# Strvo_Tester_STM_v4.net
KiCad netlist of a schematic drawn in EAGLE
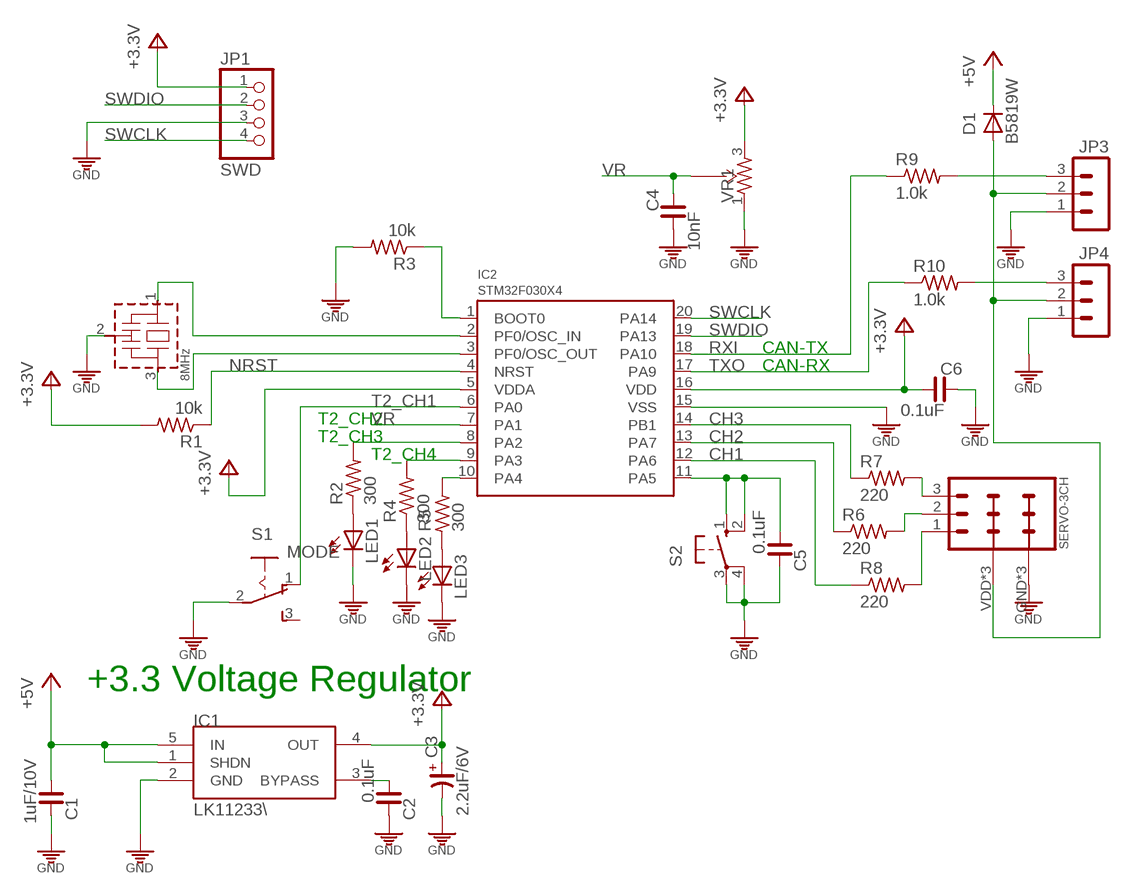
[diagram p0: schematic, sheet 1]

(export (version "E")
  (design (tool "Eeschema 10.0.6"))
  (components
    (comp (ref "C1")
      (value "1uF/10V")
      (footprint "eagle-import:C0603")
      (libsource (lib "eagle-import") (part "C_0603"))
    )
    (comp (ref "C2")
      (value "0.1uF")
      (footprint "eagle-import:C0603")
      (libsource (lib "eagle-import") (part "C_0603"))
    )
    (comp (ref "C3")
      (value "2.2uF/6V")
      (footprint "eagle-import:C2012_T")
      (libsource (lib "eagle-import") (part "CP_2012"))
    )
    (comp (ref "C4")
      (value "10nF")
      (footprint "eagle-import:C0603")
      (libsource (lib "eagle-import") (part "C_0603"))
    )
    (comp (ref "C5")
      (value "0.1uF")
      (footprint "eagle-import:C0603")
      (libsource (lib "eagle-import") (part "C_0603"))
    )
    (comp (ref "C6")
      (value "0.1uF")
      (footprint "eagle-import:C0603")
      (libsource (lib "eagle-import") (part "C_0603"))
    )
    (comp (ref "D1")
      (value "B5819W")
      (footprint "eagle-import:SOD323")
      (libsource (lib "eagle-import") (part "B5189WN"))
    )
    (comp (ref "IC1")
      (value "LK11233\\")
      (footprint "eagle-import:SOT23-5L")
      (libsource (lib "eagle-import") (part "LK112XX"))
    )
    (comp (ref "IC2")
      (value "STM32F030X4")
      (footprint "eagle-import:TSSOP20")
      (libsource (lib "eagle-import") (part "STM32F030X4"))
    )
    (comp (ref "JP1")
      (value "SWD")
      (footprint "eagle-import:1X04M")
      (libsource (lib "eagle-import") (part "PINHD-1X4M"))
    )
    (comp (ref "JP2")
      (value "SERVO-3CH")
      (footprint "eagle-import:SERVO-3CH1")
      (libsource (lib "eagle-import") (part "SERVO-3CH"))
    )
    (comp (ref "JP3")
      (value "MA03-1SMALL")
      (footprint "eagle-import:MA03-1-S")
      (libsource (lib "eagle-import") (part "MA03-1SMALL"))
    )
    (comp (ref "JP4")
      (value "MA03-1SMALL")
      (footprint "eagle-import:MA03-1-S")
      (libsource (lib "eagle-import") (part "MA03-1SMALL"))
    )
    (comp (ref "LED1")
      (value "LED3MM")
      (footprint "eagle-import:LED3MM")
      (libsource (lib "eagle-import") (part "LED3MM"))
    )
    (comp (ref "LED2")
      (value "LED3MM")
      (footprint "eagle-import:LED3MM")
      (libsource (lib "eagle-import") (part "LED3MM"))
    )
    (comp (ref "LED3")
      (value "LED3MM")
      (footprint "eagle-import:LED3MM")
      (libsource (lib "eagle-import") (part "LED3MM"))
    )
    (comp (ref "Q1")
      (value "8MHz")
      (footprint "eagle-import:CSTLA_X")
      (libsource (lib "eagle-import") (part "X-TAL-SMALLCSTCE16M00V53"))
    )
    (comp (ref "R1")
      (value "10k")
      (footprint "eagle-import:R0603")
      (libsource (lib "eagle-import") (part "R-US_R1608"))
    )
    (comp (ref "R2")
      (value "300")
      (footprint "eagle-import:R0603")
      (libsource (lib "eagle-import") (part "R-US_R1608"))
    )
    (comp (ref "R3")
      (value "10k")
      (footprint "eagle-import:R0603")
      (libsource (lib "eagle-import") (part "R-US_R1608"))
    )
    (comp (ref "R4")
      (value "300")
      (footprint "eagle-import:R0603")
      (libsource (lib "eagle-import") (part "R-US_R1608"))
    )
    (comp (ref "R5")
      (value "300")
      (footprint "eagle-import:R0603")
      (libsource (lib "eagle-import") (part "R_0603"))
    )
    (comp (ref "R6")
      (value "220")
      (footprint "eagle-import:R0603")
      (libsource (lib "eagle-import") (part "R-US_R1608"))
    )
    (comp (ref "R7")
      (value "220")
      (footprint "eagle-import:R0603")
      (libsource (lib "eagle-import") (part "R-US_R1608"))
    )
    (comp (ref "R8")
      (value "220")
      (footprint "eagle-import:R0603")
      (libsource (lib "eagle-import") (part "R-US_R1608"))
    )
    (comp (ref "R9")
      (value "1.0k")
      (footprint "eagle-import:R0603")
      (libsource (lib "eagle-import") (part "R-US_R1608"))
    )
    (comp (ref "R10")
      (value "1.0k")
      (footprint "eagle-import:R0603")
      (libsource (lib "eagle-import") (part "R-US_R1608"))
    )
    (comp (ref "S1")
      (value "MODE")
      (footprint "eagle-import:255SB")
      (libsource (lib "eagle-import") (part "IMMS"))
    )
    (comp (ref "S2")
      (value "10-XX")
      (footprint "eagle-import:B3F-10XX")
      (fields (field (name "MPN") "B3F-1000"))
      (libsource (lib "eagle-import") (part "10-XX"))
    )
    (comp (ref "VR1")
      (value "R-TRIMMER-SMDPTV")
      (footprint "eagle-import:PTV09")
      (libsource (lib "eagle-import") (part "R-TRIMMER-SMDPTV"))
    )
  )
  (nets
    (net (code "1") (name "+3V3") (class "Default")
      (node (ref "C3") (pin "+") (pinfunction "+_+") (pintype "passive"))
      (node (ref "C6") (pin "2") (pinfunction "2_2") (pintype "passive"))
      (node (ref "IC1") (pin "4") (pinfunction "OUT_4") (pintype "power_in"))
      (node (ref "IC2") (pin "16") (pinfunction "VDD_16") (pintype "power_in"))
      (node (ref "IC2") (pin "5") (pinfunction "VDDA_5") (pintype "power_in"))
      (node (ref "JP1") (pin "1") (pinfunction "1_1") (pintype "passive"))
      (node (ref "R1") (pin "2") (pinfunction "2_2") (pintype "passive"))
      (node (ref "VR1") (pin "3") (pinfunction "3_3") (pintype "passive"))
    )
    (net (code "2") (name "+5V") (class "Default")
      (node (ref "C1") (pin "2") (pinfunction "2_2") (pintype "passive"))
      (node (ref "D1") (pin "C") (pinfunction "C_C") (pintype "passive"))
      (node (ref "IC1") (pin "1") (pinfunction "SHDN_1") (pintype "passive"))
      (node (ref "IC1") (pin "5") (pinfunction "IN_5") (pintype "power_in"))
    )
    (net (code "3") (name "/CH1") (class "Default")
      (node (ref "IC2") (pin "12") (pinfunction "PA6_12") (pintype "bidirectional"))
      (node (ref "R8") (pin "1") (pinfunction "1_1") (pintype "passive"))
    )
    (net (code "4") (name "/CH2") (class "Default")
      (node (ref "IC2") (pin "13") (pinfunction "PA7_13") (pintype "bidirectional"))
      (node (ref "R6") (pin "1") (pinfunction "1_1") (pintype "passive"))
    )
    (net (code "5") (name "/CH3") (class "Default")
      (node (ref "IC2") (pin "14") (pinfunction "PB1_14") (pintype "bidirectional"))
      (node (ref "R7") (pin "1") (pinfunction "1_1") (pintype "passive"))
    )
    (net (code "6") (name "/NRST") (class "Default")
      (node (ref "IC2") (pin "4") (pinfunction "NRST_4") (pintype "bidirectional"))
      (node (ref "R1") (pin "1") (pinfunction "1_1") (pintype "passive"))
    )
    (net (code "7") (name "/RXI") (class "Default")
      (node (ref "IC2") (pin "18") (pinfunction "PA10_18") (pintype "bidirectional"))
      (node (ref "R9") (pin "1") (pinfunction "1_1") (pintype "passive"))
    )
    (net (code "8") (name "/SWCLK") (class "Default")
      (node (ref "IC2") (pin "20") (pinfunction "PA14_20") (pintype "bidirectional"))
      (node (ref "JP1") (pin "4") (pinfunction "4_4") (pintype "passive"))
    )
    (net (code "9") (name "/SWDIO") (class "Default")
      (node (ref "IC2") (pin "19") (pinfunction "PA13_19") (pintype "bidirectional"))
      (node (ref "JP1") (pin "2") (pinfunction "2_2") (pintype "passive"))
    )
    (net (code "10") (name "/T2_CH1") (class "Default")
      (node (ref "IC2") (pin "6") (pinfunction "PA0_6") (pintype "bidirectional"))
      (node (ref "S1") (pin "1") (pinfunction "O_1") (pintype "passive"))
    )
    (net (code "11") (name "/TXO") (class "Default")
      (node (ref "IC2") (pin "17") (pinfunction "PA9_17") (pintype "bidirectional"))
      (node (ref "R10") (pin "1") (pinfunction "1_1") (pintype "passive"))
    )
    (net (code "12") (name "/VR") (class "Default")
      (node (ref "C4") (pin "1") (pinfunction "1_1") (pintype "passive"))
      (node (ref "IC2") (pin "7") (pinfunction "PA1_7") (pintype "bidirectional"))
      (node (ref "VR1") (pin "2") (pinfunction "2_2") (pintype "passive"))
    )
    (net (code "13") (name "GND") (class "Default")
      (node (ref "C1") (pin "1") (pinfunction "1_1") (pintype "passive"))
      (node (ref "C2") (pin "1") (pinfunction "1_1") (pintype "passive"))
      (node (ref "C3") (pin "-") (pinfunction "-_-") (pintype "passive"))
      (node (ref "C4") (pin "2") (pinfunction "2_2") (pintype "passive"))
      (node (ref "C5") (pin "1") (pinfunction "1_1") (pintype "passive"))
      (node (ref "C6") (pin "1") (pinfunction "1_1") (pintype "passive"))
      (node (ref "IC1") (pin "2") (pinfunction "GND_2") (pintype "power_in"))
      (node (ref "IC2") (pin "15") (pinfunction "VSS_15") (pintype "power_in"))
      (node (ref "JP1") (pin "3") (pinfunction "3_3") (pintype "passive"))
      (node (ref "JP2") (pin "GND") (pinfunction "GND_GND") (pintype "passive"))
      (node (ref "JP2") (pin "GND@1") (pinfunction "GND_GND@1") (pintype "passive"))
      (node (ref "JP2") (pin "GND@2") (pinfunction "GND_GND@2") (pintype "passive"))
      (node (ref "JP3") (pin "1") (pinfunction "1_1") (pintype "passive"))
      (node (ref "JP4") (pin "1") (pinfunction "1_1") (pintype "passive"))
      (node (ref "LED1") (pin "K") (pinfunction "C_K") (pintype "passive"))
      (node (ref "LED2") (pin "K") (pinfunction "C_K") (pintype "passive"))
      (node (ref "LED3") (pin "K") (pinfunction "C_K") (pintype "passive"))
      (node (ref "Q1") (pin "2") (pinfunction "GND_2") (pintype "power_in"))
      (node (ref "R3") (pin "2") (pinfunction "2_2") (pintype "passive"))
      (node (ref "S1") (pin "2") (pinfunction "P_2") (pintype "passive"))
      (node (ref "S2") (pin "3") (pinfunction "P_3") (pintype "passive"))
      (node (ref "S2") (pin "4") (pinfunction "P1_4") (pintype "passive"))
      (node (ref "VR1") (pin "1") (pinfunction "1_1") (pintype "passive"))
    )
    (net (code "14") (name "Net-(D1-PadA)") (class "Default")
      (node (ref "D1") (pin "A") (pinfunction "A_A") (pintype "passive"))
      (node (ref "JP2") (pin "VDD") (pinfunction "+5V_VDD") (pintype "passive"))
      (node (ref "JP2") (pin "VDD@1") (pinfunction "+5V_VDD@1") (pintype "passive"))
      (node (ref "JP2") (pin "VDD@2") (pinfunction "+5V_VDD@2") (pintype "passive"))
      (node (ref "JP3") (pin "2") (pinfunction "2_2") (pintype "passive"))
      (node (ref "JP4") (pin "2") (pinfunction "2_2") (pintype "passive"))
    )
    (net (code "15") (name "Net-(IC1-BYPASS)") (class "Default")
      (node (ref "C2") (pin "2") (pinfunction "2_2") (pintype "passive"))
      (node (ref "IC1") (pin "3") (pinfunction "BYPASS_3") (pintype "passive"))
    )
    (net (code "16") (name "Net-(IC2-BOOT0)") (class "Default")
      (node (ref "IC2") (pin "1") (pinfunction "BOOT0_1") (pintype "bidirectional"))
      (node (ref "R3") (pin "1") (pinfunction "1_1") (pintype "passive"))
    )
    (net (code "17") (name "Net-(IC2-PA2)") (class "Default")
      (node (ref "IC2") (pin "8") (pinfunction "PA2_8") (pintype "bidirectional"))
      (node (ref "R2") (pin "2") (pinfunction "2_2") (pintype "passive"))
    )
    (net (code "18") (name "Net-(IC2-PA3)") (class "Default")
      (node (ref "IC2") (pin "9") (pinfunction "PA3_9") (pintype "bidirectional"))
      (node (ref "R4") (pin "2") (pinfunction "2_2") (pintype "passive"))
    )
    (net (code "19") (name "Net-(IC2-PA4)") (class "Default")
      (node (ref "IC2") (pin "10") (pinfunction "PA4_10") (pintype "bidirectional"))
      (node (ref "R5") (pin "2") (pinfunction "2_2") (pintype "passive"))
    )
    (net (code "20") (name "Net-(IC2-PA5)") (class "Default")
      (node (ref "C5") (pin "2") (pinfunction "2_2") (pintype "passive"))
      (node (ref "IC2") (pin "11") (pinfunction "PA5_11") (pintype "bidirectional"))
      (node (ref "S2") (pin "1") (pinfunction "S_1") (pintype "passive"))
      (node (ref "S2") (pin "2") (pinfunction "S1_2") (pintype "passive"))
    )
    (net (code "21") (name "Net-(IC2-PF0{slash}OSC_IN)") (class "Default")
      (node (ref "IC2") (pin "2") (pinfunction "PF0/OSC_IN_2") (pintype "bidirectional"))
      (node (ref "Q1") (pin "1") (pinfunction "IN_1") (pintype "output"))
    )
    (net (code "22") (name "Net-(IC2-PF0{slash}OSC_OUT)") (class "Default")
      (node (ref "IC2") (pin "3") (pinfunction "PF0/OSC_OUT_3") (pintype "bidirectional"))
      (node (ref "Q1") (pin "3") (pinfunction "OUT_3") (pintype "input"))
    )
    (net (code "23") (name "Net-(JP2-Pad1)") (class "Default")
      (node (ref "JP2") (pin "1") (pinfunction "1_1") (pintype "passive"))
      (node (ref "R8") (pin "2") (pinfunction "2_2") (pintype "passive"))
    )
    (net (code "24") (name "Net-(JP2-Pad2)") (class "Default")
      (node (ref "JP2") (pin "2") (pinfunction "2_2") (pintype "passive"))
      (node (ref "R6") (pin "2") (pinfunction "2_2") (pintype "passive"))
    )
    (net (code "25") (name "Net-(JP2-Pad3)") (class "Default")
      (node (ref "JP2") (pin "3") (pinfunction "3_3") (pintype "passive"))
      (node (ref "R7") (pin "2") (pinfunction "2_2") (pintype "passive"))
    )
    (net (code "26") (name "Net-(JP3-Pad3)") (class "Default")
      (node (ref "JP3") (pin "3") (pinfunction "3_3") (pintype "passive"))
      (node (ref "R9") (pin "2") (pinfunction "2_2") (pintype "passive"))
    )
    (net (code "27") (name "Net-(JP4-Pad3)") (class "Default")
      (node (ref "JP4") (pin "3") (pinfunction "3_3") (pintype "passive"))
      (node (ref "R10") (pin "2") (pinfunction "2_2") (pintype "passive"))
    )
    (net (code "28") (name "Net-(LED1-PadA)") (class "Default")
      (node (ref "LED1") (pin "A") (pinfunction "A_A") (pintype "passive"))
      (node (ref "R2") (pin "1") (pinfunction "1_1") (pintype "passive"))
    )
    (net (code "29") (name "Net-(LED2-PadA)") (class "Default")
      (node (ref "LED2") (pin "A") (pinfunction "A_A") (pintype "passive"))
      (node (ref "R4") (pin "1") (pinfunction "1_1") (pintype "passive"))
    )
    (net (code "30") (name "Net-(LED3-PadA)") (class "Default")
      (node (ref "LED3") (pin "A") (pinfunction "A_A") (pintype "passive"))
      (node (ref "R5") (pin "1") (pinfunction "1_1") (pintype "passive"))
    )
    (net (code "31") (name "unconnected-(S1-S-Pad3)") (class "Default")
      (node (ref "S1") (pin "3") (pinfunction "S_3") (pintype "passive"))
    )
  )
)
